# wind_vane.net
KiCad netlist of a schematic drawn in EAGLE
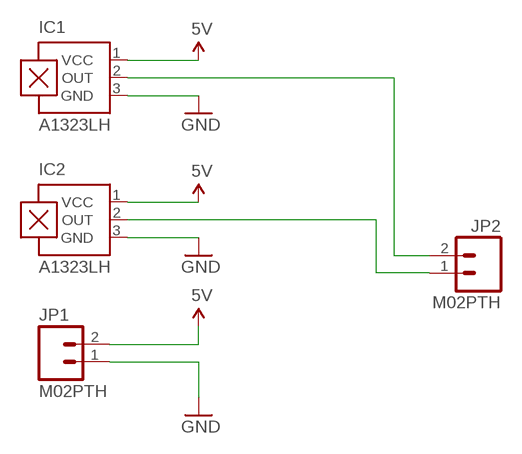
[diagram p0: schematic, sheet 1]

(export (version "E")
  (design (tool "Eeschema 10.0.6"))
  (components
    (comp (ref "IC1")
      (value "A1323LH")
      (footprint "eagle-import:SOT23-W")
      (fields (field (name "MF") "ALLEGRO MICROSYSTEMS, INC.") (field (name "MPN") "A1323LLHLT-T"))
      (libsource (lib "eagle-import") (part "A13?LH23"))
    )
    (comp (ref "IC2")
      (value "A1323LH")
      (footprint "eagle-import:SOT23-W")
      (fields (field (name "MF") "ALLEGRO MICROSYSTEMS, INC.") (field (name "MPN") "A1323LLHLT-T"))
      (libsource (lib "eagle-import") (part "A13?LH23"))
    )
    (comp (ref "JP1")
      (value "M02PTH")
      (footprint "eagle-import:1X02")
      (libsource (lib "eagle-import") (part "M02PTH"))
    )
    (comp (ref "JP2")
      (value "M02PTH")
      (footprint "eagle-import:1X02")
      (libsource (lib "eagle-import") (part "M02PTH"))
    )
  )
  (nets
    (net (code "1") (name "5V") (class "Default")
      (node (ref "IC1") (pin "1") (pinfunction "VCC_1") (pintype "power_in"))
      (node (ref "IC2") (pin "1") (pinfunction "VCC_1") (pintype "power_in"))
      (node (ref "JP1") (pin "2") (pinfunction "2_2") (pintype "passive"))
    )
    (net (code "2") (name "GND") (class "Default")
      (node (ref "IC1") (pin "3") (pinfunction "GND_3") (pintype "power_in"))
      (node (ref "IC2") (pin "3") (pinfunction "GND_3") (pintype "power_in"))
      (node (ref "JP1") (pin "1") (pinfunction "1_1") (pintype "passive"))
    )
    (net (code "3") (name "Net-(IC1-OUT)") (class "Default")
      (node (ref "IC1") (pin "2") (pinfunction "OUT_2") (pintype "output"))
      (node (ref "JP2") (pin "2") (pinfunction "2_2") (pintype "passive"))
    )
    (net (code "4") (name "Net-(IC2-OUT)") (class "Default")
      (node (ref "IC2") (pin "2") (pinfunction "OUT_2") (pintype "output"))
      (node (ref "JP2") (pin "1") (pinfunction "1_1") (pintype "passive"))
    )
  )
)
